# sch.net
KiCad netlist of a schematic drawn in Altium Designer
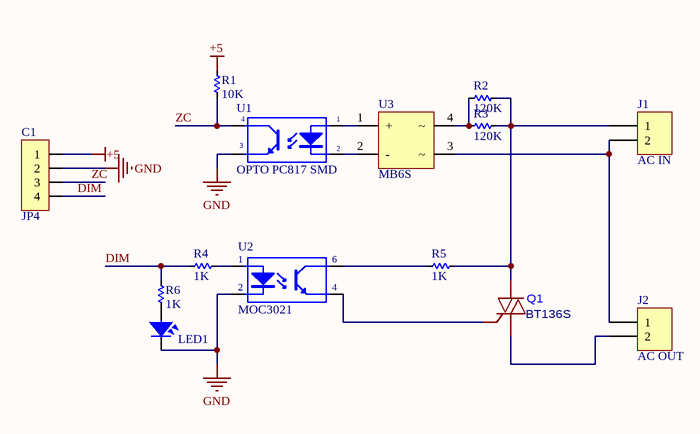
[diagram p0: sch.SchDoc]

(export (version "E")
  (design (tool "Eeschema 10.0.6"))
  (components
    (comp (ref "C1")
      (value "JP4")
      (footprint "JP4-D1C")
      (description "WR-PHD 2.54 mm Angled Socket Header")
      (fields
        (field (name "MANUFACTURER") "Würth Elektronik eiSos GmbH")
        (field (name "PARTNO") "613004143121")
        (field (name "CREATED BY") "Karrer Zheng")
      )
      (libsource (lib "LIBRARY1") (part "JP4"))
    )
    (comp (ref "J1")
      (value "AC IN")
      (footprint "CON 2 2EDG5.08")
      (description "CON2 KF terminal")
      (libsource (lib "iuh-thuc-hanh") (part "CON 2"))
    )
    (comp (ref "J2")
      (value "AC OUT")
      (footprint "CON 2 2EDG5.08")
      (description "CON2 KF terminal")
      (libsource (lib "iuh-thuc-hanh") (part "CON 2"))
    )
    (comp (ref "LED1") (value "LED") (footprint "LED-0805-Red") (libsource (lib "LIBRARY1") (part "LED SMD")))
    (comp (ref "Q1")
      (value "BT136S")
      (footprint "TO-252-3_L6.6-W6.1-P4.57-LS9.9-BR-CW")
      (libsource (lib "Altium_Lib_by_KhueNguyenCreator") (part "BT136-800E_C2901010"))
    )
    (comp (ref "R1")
      (value "10K")
      (footprint "RES-SMD-0805")
      (description "Resistor")
      (fields
        (field (name "MANUFACTURER") "Generic Components")
        (field (name "PUBLISHER") "Altium Hobart Technology Centre")
      )
      (libsource (lib "LIBRARY1") (part "Res-SMD"))
    )
    (comp (ref "R2")
      (value "120K")
      (footprint "RES-SMD-1210")
      (description "Resistor")
      (fields
        (field (name "MANUFACTURER") "Generic Components")
        (field (name "PUBLISHER") "Altium Hobart Technology Centre")
      )
      (libsource (lib "LIBRARY1") (part "Res-SMD"))
    )
    (comp (ref "R3")
      (value "120K")
      (footprint "RES-SMD-1210")
      (description "Resistor")
      (fields
        (field (name "MANUFACTURER") "Generic Components")
        (field (name "PUBLISHER") "Altium Hobart Technology Centre")
      )
      (libsource (lib "LIBRARY1") (part "Res-SMD"))
    )
    (comp (ref "R4")
      (value "1K")
      (footprint "RES-SMD-0805")
      (description "Resistor")
      (fields
        (field (name "MANUFACTURER") "Generic Components")
        (field (name "PUBLISHER") "Altium Hobart Technology Centre")
      )
      (libsource (lib "LIBRARY1") (part "Res-SMD"))
    )
    (comp (ref "R5")
      (value "1K")
      (footprint "RES-SMD-0805")
      (description "Resistor")
      (fields
        (field (name "MANUFACTURER") "Generic Components")
        (field (name "PUBLISHER") "Altium Hobart Technology Centre")
      )
      (libsource (lib "LIBRARY1") (part "Res-SMD"))
    )
    (comp (ref "R6")
      (value "1K")
      (footprint "RES-SMD-0805")
      (description "Resistor")
      (fields
        (field (name "MANUFACTURER") "Generic Components")
        (field (name "PUBLISHER") "Altium Hobart Technology Centre")
      )
      (libsource (lib "LIBRARY1") (part "Res-SMD"))
    )
    (comp (ref "U1")
      (value "OPTO PC817 SMD")
      (footprint "SOP4")
      (description "Single Opto")
      (libsource (lib "Altium_Lib_by_KhueNguyenCreator") (part "OPTO PC817 SMD"))
    )
    (comp (ref "U2")
      (value "MOC3021")
      (footprint "SO6")
      (description "Single Opto")
      (libsource (lib "LIBRARY1") (part "MOC3021"))
    )
    (comp (ref "U3")
      (value "MB6S")
      (footprint "TO269AA")
      (description "Bridge Rectifier")
      (libsource (lib "iuh-thuc-hanh") (part "MB6S"))
    )
  )
  (nets
    (net (code "1") (name "+5") (class "Default")
      (node (ref "C1") (pin "1") (pinfunction "1_1") (pintype "passive"))
      (node (ref "R1") (pin "1") (pinfunction "1_1") (pintype "passive"))
    )
    (net (code "2") (name "/DIM") (class "Default")
      (node (ref "C1") (pin "4") (pinfunction "4_4") (pintype "passive"))
      (node (ref "R4") (pin "2") (pinfunction "2_2") (pintype "passive"))
      (node (ref "R6") (pin "1") (pinfunction "1_1") (pintype "passive"))
    )
    (net (code "3") (name "/ZC") (class "Default")
      (node (ref "C1") (pin "3") (pinfunction "3_3") (pintype "passive"))
      (node (ref "R1") (pin "2") (pinfunction "2_2") (pintype "passive"))
      (node (ref "U1") (pin "4") (pinfunction "C_4") (pintype "passive"))
    )
    (net (code "4") (name "GND") (class "Default")
      (node (ref "C1") (pin "2") (pinfunction "2_2") (pintype "passive"))
      (node (ref "LED1") (pin "2") (pinfunction "2_2") (pintype "passive"))
      (node (ref "U1") (pin "3") (pinfunction "E_3") (pintype "passive"))
      (node (ref "U2") (pin "2") (pinfunction "K_2") (pintype "passive"))
    )
    (net (code "5") (name "Net-(J1-Pad2)") (class "Default")
      (node (ref "J1") (pin "2") (pinfunction "2_2") (pintype "passive"))
      (node (ref "J2") (pin "1") (pinfunction "1_1") (pintype "passive"))
      (node (ref "U3") (pin "3") (pinfunction "~_3") (pintype "passive"))
    )
    (net (code "6") (name "Net-(LED1-Pad1)") (class "Default")
      (node (ref "LED1") (pin "1") (pinfunction "1_1") (pintype "passive"))
      (node (ref "R6") (pin "2") (pinfunction "2_2") (pintype "passive"))
    )
    (net (code "7") (name "Net-(Q1-G)") (class "Default")
      (node (ref "Q1") (pin "3") (pinfunction "G_3") (pintype "passive"))
      (node (ref "U2") (pin "4") (pinfunction "E_4") (pintype "passive"))
    )
    (net (code "8") (name "Net-(Q1-T1)") (class "Default")
      (node (ref "J2") (pin "2") (pinfunction "2_2") (pintype "passive"))
      (node (ref "Q1") (pin "1") (pinfunction "T1_1") (pintype "passive"))
    )
    (net (code "9") (name "Net-(Q1-T2)") (class "Default")
      (node (ref "J1") (pin "1") (pinfunction "1_1") (pintype "passive"))
      (node (ref "Q1") (pin "2") (pinfunction "T2_2") (pintype "passive"))
      (node (ref "R2") (pin "1") (pinfunction "1_1") (pintype "passive"))
      (node (ref "R3") (pin "1") (pinfunction "1_1") (pintype "passive"))
      (node (ref "R5") (pin "1") (pinfunction "1_1") (pintype "passive"))
    )
    (net (code "10") (name "Net-(R2-Pad2)") (class "Default")
      (node (ref "R2") (pin "2") (pinfunction "2_2") (pintype "passive"))
      (node (ref "R3") (pin "2") (pinfunction "2_2") (pintype "passive"))
      (node (ref "U3") (pin "4") (pinfunction "~_4") (pintype "passive"))
    )
    (net (code "11") (name "Net-(U1-A)") (class "Default")
      (node (ref "U1") (pin "1") (pinfunction "A_1") (pintype "passive"))
      (node (ref "U3") (pin "1") (pinfunction "+_1") (pintype "passive"))
    )
    (net (code "12") (name "Net-(U1-K)") (class "Default")
      (node (ref "U1") (pin "2") (pinfunction "K_2") (pintype "passive"))
      (node (ref "U3") (pin "2") (pinfunction "-_2") (pintype "passive"))
    )
    (net (code "13") (name "Net-(U2-A)") (class "Default")
      (node (ref "R4") (pin "1") (pinfunction "1_1") (pintype "passive"))
      (node (ref "U2") (pin "1") (pinfunction "A_1") (pintype "passive"))
    )
    (net (code "14") (name "Net-(U2-C)") (class "Default")
      (node (ref "R5") (pin "2") (pinfunction "2_2") (pintype "passive"))
      (node (ref "U2") (pin "6") (pinfunction "C_6") (pintype "passive"))
    )
  )
)
